# pqm_v2_page1.net
KiCad netlist of a schematic drawn in Altium Designer
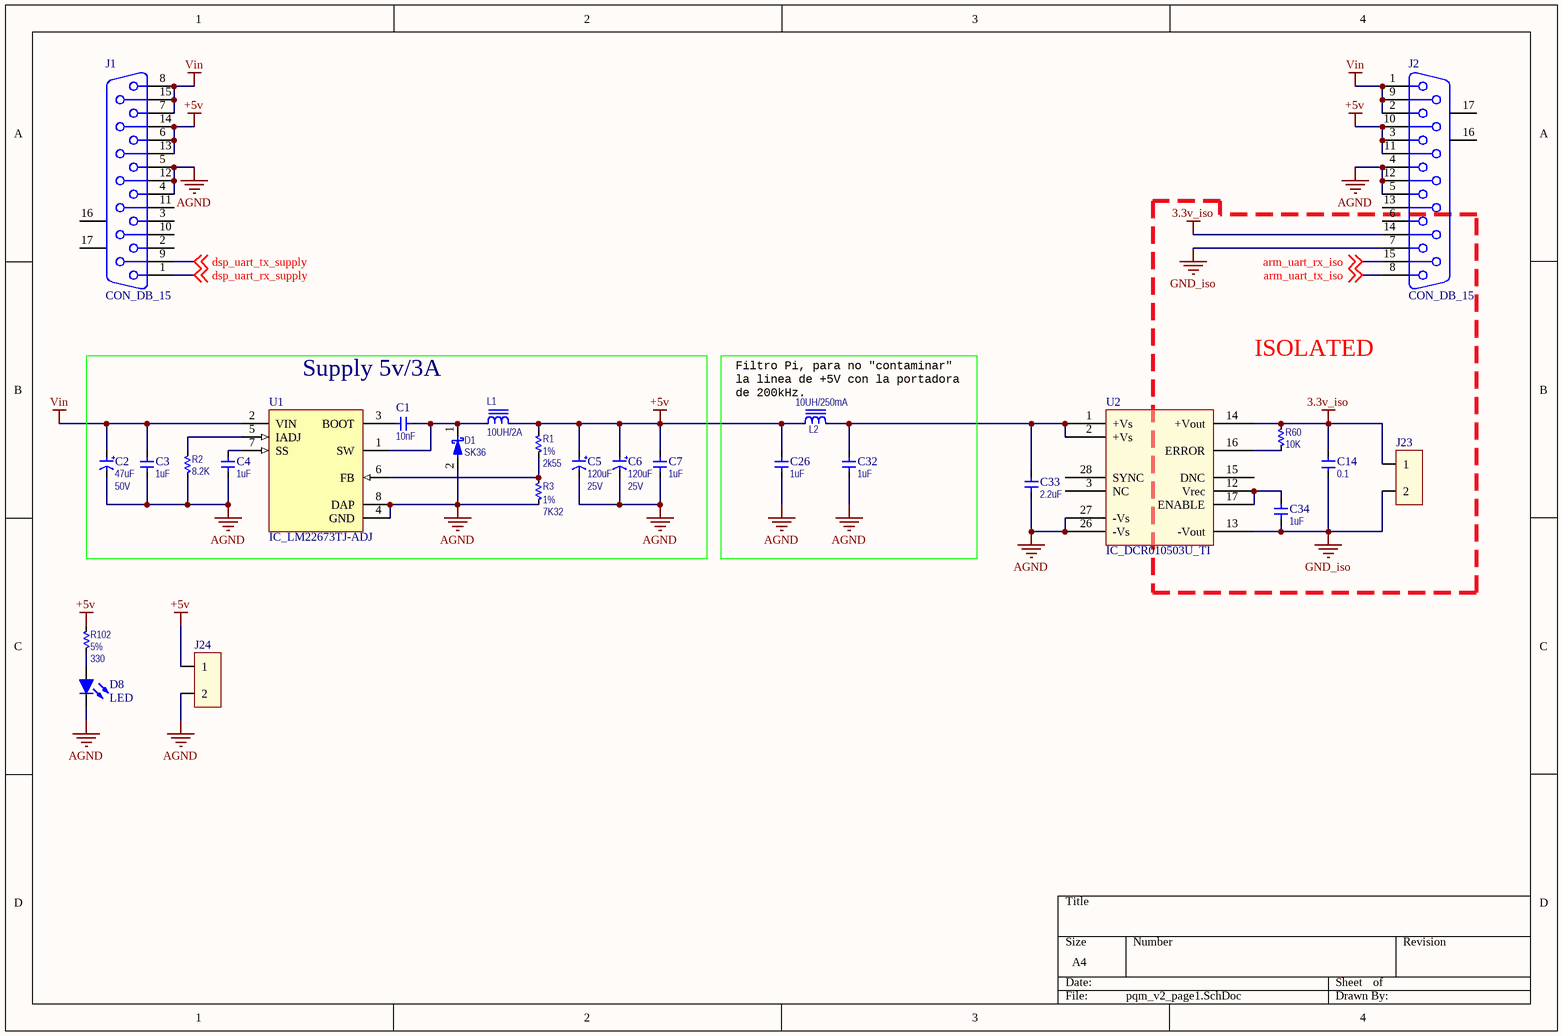
[diagram p0: pqm_v2_page1.SchDoc]

(export (version "E")
  (design (tool "Eeschema 10.0.6"))
  (components
    (comp (ref "C1")
      (value "10nF")
      (footprint "CAPC3216X135N_B")
      (fields
        (field (name "MANUFACTURER") "TDK")
        (field (name "TOLERANCE") "10%")
        (field (name "DIGIKEY PART NUMBER") "445-2291-1-ND")
      )
      (libsource (lib "pqm_v2_lib_cap") (part "CAP_C3216X7R2J103K115AA_TDK"))
    )
    (comp (ref "C2")
      (value "47uF")
      (footprint "CAPAE630770X770N")
      (description "47µF 50V Aluminum Capacitors Radial, Can - SMD 2000 Hrs @ 85°C")
      (fields
        (field (name "MANUFACTURER") "Panasonic")
        (field (name "TOLERANCE") "20%")
        (field (name "VOLTAGE RATING") "50V")
      )
      (libsource (lib "pqm_v2_lib_cap") (part "CAP_EEE-1HA470XP_PANASONIC"))
    )
    (comp (ref "C3")
      (value "1uF")
      (footprint "CAPC3216X135N_B")
      (fields
        (field (name "MANUFACTURER") "TDK")
        (field (name "TOLERANCE") "20%")
        (field (name "DIGIKEY PART NUMBER") "445-4024-1-ND")
      )
      (libsource (lib "pqm_v2_lib_cap") (part "CAP_C3216X7R1E105M085AA_TDK"))
    )
    (comp (ref "C4")
      (value "1uF")
      (footprint "CAPC3216X135N_B")
      (fields
        (field (name "MANUFACTURER") "TDK")
        (field (name "TOLERANCE") "20%")
        (field (name "DIGIKEY PART NUMBER") "445-4024-1-ND")
      )
      (libsource (lib "pqm_v2_lib_cap") (part "CAP_C3216X7R1E105M085AA_TDK"))
    )
    (comp (ref "C5")
      (value "120uF")
      (footprint "CAPPRD250W50D630H1250")
      (description "CAP ALUM 120UF 20% 25V RADIAL")
      (fields
        (field (name "DIGIKEY PART NUMBER") "565-1791-ND")
        (field (name "TOLERANCE") "20%")
        (field (name "VOLTAGE RATING") "25V")
      )
      (libsource (lib "pqm_v2_lib_cap") (part "CAP_ELXY250ELL121MF15D_UC"))
    )
    (comp (ref "C6")
      (value "120uF")
      (footprint "CAPPRD250W50D630H1250")
      (description "CAP ALUM 120UF 20% 25V RADIAL")
      (fields
        (field (name "DIGIKEY PART NUMBER") "565-1791-ND")
        (field (name "TOLERANCE") "20%")
        (field (name "VOLTAGE RATING") "25V")
      )
      (libsource (lib "pqm_v2_lib_cap") (part "CAP_ELXY250ELL121MF15D_UC"))
    )
    (comp (ref "C7")
      (value "1uF")
      (footprint "CAPC3216X135N_B")
      (fields
        (field (name "MANUFACTURER") "TDK")
        (field (name "TOLERANCE") "20%")
        (field (name "DIGIKEY PART NUMBER") "445-4024-1-ND")
      )
      (libsource (lib "pqm_v2_lib_cap") (part "CAP_C3216X7R1E105M085AA_TDK"))
    )
    (comp (ref "C14")
      (value "0.1")
      (footprint "CAPC2013X110N")
      (description "CAP CER 0.1UF 25V 10% X7R 0805")
      (fields (field (name "MANUFACTURER") "Yageo") (field (name "TOLERANCE") "10%"))
      (libsource (lib "pqm_v2_lib_cap") (part "CAP_CC0805KRX7R8BB104_YAGEO"))
    )
    (comp (ref "C26")
      (value "1uF")
      (footprint "CAPC3216X135N_B")
      (fields
        (field (name "MANUFACTURER") "TDK")
        (field (name "TOLERANCE") "20%")
        (field (name "DIGIKEY PART NUMBER") "445-4024-1-ND")
      )
      (libsource (lib "pqm_v2_lib_cap") (part "CAP_C3216X7R1E105M085AA_TDK"))
    )
    (comp (ref "C32")
      (value "1uF")
      (footprint "CAPC3216X135N_B")
      (fields
        (field (name "MANUFACTURER") "TDK")
        (field (name "TOLERANCE") "20%")
        (field (name "DIGIKEY PART NUMBER") "445-4024-1-ND")
      )
      (libsource (lib "pqm_v2_lib_cap") (part "CAP_C3216X7R1E105M085AA_TDK"))
    )
    (comp (ref "C33")
      (value "2.2uF")
      (footprint "CAPC3216X135N_B")
      (description "CAP CER 2.2UF 16V X7R 1206")
      (fields (field (name "MANUFACTURER") "YAGEO") (field (name "TOLERANCE") "10%"))
      (libsource (lib "pqm_v2_lib_cap") (part "CAP_CC1206KKX7R7BB225_YAGEO"))
    )
    (comp (ref "C34")
      (value "1uF")
      (footprint "CAPC2013X110N")
      (description "CAP CER 1UF 16V X7R 0805")
      (fields (field (name "MANUFACTURER") "YAGEO") (field (name "TOLERANCE") "10%"))
      (libsource (lib "pqm_v2_lib_cap") (part "CAP_CC0805KKX7R7BB105_YAGEO"))
    )
    (comp (ref "D1")
      (value "SK36")
      (footprint "DIOM7959X262N")
      (description "DIODE SCHOTTKY 60V 3A SMC")
      (fields
        (field (name "MANUFACTURER") "Micro Commercial Co")
        (field (name "DIGIKEY PART NUMBER") "SK36-TPMSCT-ND")
      )
      (libsource (lib "pqm_v2_lib_diodos") (part "DIO_SK36_MICROCOM"))
    )
    (comp (ref "D8")
      (value "LED")
      (footprint "Led")
      (fields (field (name "PUBLISHER") "Altium Limited"))
      (libsource (lib "pqm_v2_lib_diodos") (part "LED0"))
    )
    (comp (ref "J1")
      (value "CON_DB_15")
      (footprint "788757-1")
      (description "Receptacle Assembly, 15 Position, Right Angle, 8.08mm Series, Amplimite, with Screwlocks")
      (fields (field (name "PUBLISHER") "Altium Limited"))
      (libsource (lib "pqm_v2_lib_connectors") (part "788781-1"))
    )
    (comp (ref "J2")
      (value "CON_DB_15")
      (footprint "788757-1")
      (description "Receptacle Assembly, 15 Position, Right Angle, 8.08mm Series, Amplimite, with Screwlocks")
      (fields (field (name "PUBLISHER") "Altium Limited"))
      (libsource (lib "pqm_v2_lib_connectors") (part "788781-1"))
    )
    (comp (ref "J23")
      (value "CON_RADX2")
      (footprint "RAD2")
      (libsource (lib "pqm_v2_lib_connectors") (part "CON_RADX2"))
    )
    (comp (ref "J24")
      (value "CON_RADX2")
      (footprint "RAD2")
      (libsource (lib "pqm_v2_lib_connectors") (part "CON_RADX2"))
    )
    (comp (ref "L1")
      (value "10UH/2A")
      (footprint "MAG_INDUCTOR2A")
      (description "FIXED IND 10UH 2A 65 MOHM SMD")
      (fields
        (field (name "MANUFACTURER") "Bourns Inc")
        (field (name "DIGIKEY PART NUMBER") "SRR1005-100MCT-ND")
      )
      (libsource (lib "pqm_v2_lib_mag") (part "MAG_SRR1005-100M_BOURNS"))
    )
    (comp (ref "L2")
      (value "10UH/250mA")
      (footprint "INDC4532X170N")
      (description "FIXED IND 10UH 2A 65 MOHM SMD")
      (fields
        (field (name "MANUFACTURER") "Bourns Inc")
        (field (name "DIGIKEY PART NUMBER") "CM453232-100KLCT-ND")
      )
      (libsource (lib "pqm_v2_lib_mag") (part "MAG_CM453232-100KLCT_BOURNS"))
    )
    (comp (ref "R1")
      (value "2k55")
      (footprint "RESC3216N")
      (description "RES SMD 2.55K OHM 1% 1/4W 1206")
      (fields
        (field (name "MANUFACTURER") "Panasonic")
        (field (name "DIGIKEY PART NUMBER") "P2.55KFCT-ND")
        (field (name "TOLERANCE") "1%")
      )
      (libsource (lib "pqm_v2_lib_res") (part "RES_ERJ-8ENF2551V_Panasonic"))
    )
    (comp (ref "R2")
      (value "8.2K")
      (footprint "RESC3216N")
      (description "RES SMD 8.2K OHM 5% 1/4W 1206")
      (fields (field (name "TOLERANCE") "5%") (field (name "MANUFACTURER") "Panasonic"))
      (libsource (lib "pqm_v2_lib_res") (part "RES_ERJ-8GEYJ822V_Panasonic"))
    )
    (comp (ref "R3")
      (value "7K32")
      (footprint "RESC3216N")
      (description "RES SMD 7.32K OHM 1% 1/4W 1206")
      (fields
        (field (name "MANUFACTURER") "Panasonic")
        (field (name "DIGIKEY PART NUMBER") "P7.32KFCT-ND")
        (field (name "TOLERANCE") "1%")
      )
      (libsource (lib "pqm_v2_lib_res") (part "RES_ERJ-8ENF7321V_Panasonic"))
    )
    (comp (ref "R60")
      (value "10K")
      (footprint "RESC3216N")
      (description "RES SMD 10K OHM 1% 1/4W 1206")
      (fields (field (name "TOLERANCE") "1%") (field (name "MANUFACTURER") "Yageo"))
      (libsource (lib "pqm_v2_lib_res") (part "RES_RC1206FR-0710KL_Yageo"))
    )
    (comp (ref "R102")
      (value "330")
      (footprint "RESC2013X065BN")
      (description "RES SMD 330 OHM 5% 1/8W 0805")
      (fields
        (field (name "MANUFACTURER") "Yageo")
        (field (name "DIGIKEY PART NUMBER") "311-330ARCT-ND")
        (field (name "TOLERANCE") "5%")
      )
      (libsource (lib "pqm_v2_lib_res") (part "RES_RC0805JR-07330RL_YAGEO"))
    )
    (comp (ref "U1")
      (value "IC_LM22673TJ-ADJ")
      (footprint "TJ7A_N")
      (fields
        (field (name "DIGIKEY PART NUMBER") "LM22673TJ-ADJ/NOPBCT-ND")
        (field (name "MANUFACTURER PART NUMBER") "LM22673TJ-ADJ/NOPB")
        (field (name "MOUSER PART NUMBER") "926-LM22673TJADJNOPB")
      )
      (libsource (lib "pqm_v2_lib_ic") (part "IC_LM22673TJ-ADJ"))
    )
    (comp (ref "U2")
      (value "IC_DCR010503U_TI")
      (footprint "SOP28")
      (description "IC REG ISOLATED 3.3V 0.3A 12SOP")
      (fields
        (field (name "DIGIKEY PART NUMBER") "296-9450-5-ND")
        (field (name "MOUSER PART NUMBER") "595-DCR010503U")
      )
      (libsource (lib "pqm_v2_lib_ic") (part "IC_DCR010503U_TI"))
    )
  )
  (nets
    (net (code "1") (name "+5v") (class "Default")
      (node (ref "C26") (pin "1") (pinfunction "T1_1") (pintype "passive"))
      (node (ref "C5") (pin "1") (pinfunction "1_1") (pintype "passive"))
      (node (ref "C6") (pin "1") (pinfunction "1_1") (pintype "passive"))
      (node (ref "C7") (pin "1") (pinfunction "T1_1") (pintype "passive"))
      (node (ref "J1") (pin "13") (pinfunction "13_13") (pintype "passive"))
      (node (ref "J1") (pin "14") (pinfunction "14_14") (pintype "passive"))
      (node (ref "J1") (pin "6") (pinfunction "6_6") (pintype "passive"))
      (node (ref "J2") (pin "10") (pinfunction "10_10") (pintype "passive"))
      (node (ref "J2") (pin "11") (pinfunction "11_11") (pintype "passive"))
      (node (ref "J2") (pin "3") (pinfunction "3_3") (pintype "passive"))
      (node (ref "J24") (pin "1") (pinfunction "1_1") (pintype "passive"))
      (node (ref "L1") (pin "2") (pinfunction "2_2") (pintype "passive"))
      (node (ref "L2") (pin "1") (pinfunction "1_1") (pintype "passive"))
      (node (ref "R1") (pin "1") (pinfunction "T1_1") (pintype "passive"))
      (node (ref "R102") (pin "2") (pinfunction "T2_2") (pintype "passive"))
    )
    (net (code "2") (name "3.3v_iso") (class "Default")
      (node (ref "C14") (pin "1") (pinfunction "T1_1") (pintype "passive"))
      (node (ref "J2") (pin "14") (pinfunction "14_14") (pintype "passive"))
      (node (ref "J23") (pin "1") (pinfunction "1_1") (pintype "passive"))
      (node (ref "R60") (pin "2") (pinfunction "T2_2") (pintype "passive"))
      (node (ref "U2") (pin "14") (pinfunction "+Vout_14") (pintype "passive"))
    )
    (net (code "3") (name "AGND") (class "Default")
      (node (ref "C2") (pin "2") (pinfunction "2_2") (pintype "passive"))
      (node (ref "C26") (pin "2") (pinfunction "T2_2") (pintype "passive"))
      (node (ref "C3") (pin "2") (pinfunction "T2_2") (pintype "passive"))
      (node (ref "C32") (pin "2") (pinfunction "T2_2") (pintype "passive"))
      (node (ref "C33") (pin "2") (pinfunction "T2_2") (pintype "passive"))
      (node (ref "C4") (pin "2") (pinfunction "T2_2") (pintype "passive"))
      (node (ref "C5") (pin "2") (pinfunction "2_2") (pintype "passive"))
      (node (ref "C6") (pin "2") (pinfunction "2_2") (pintype "passive"))
      (node (ref "C7") (pin "2") (pinfunction "T2_2") (pintype "passive"))
      (node (ref "D1") (pin "2") (pinfunction "A_2") (pintype "passive"))
      (node (ref "D8") (pin "2") (pinfunction "K_2") (pintype "passive"))
      (node (ref "J1") (pin "12") (pinfunction "12_12") (pintype "passive"))
      (node (ref "J1") (pin "4") (pinfunction "4_4") (pintype "passive"))
      (node (ref "J1") (pin "5") (pinfunction "5_5") (pintype "passive"))
      (node (ref "J2") (pin "12") (pinfunction "12_12") (pintype "passive"))
      (node (ref "J2") (pin "4") (pinfunction "4_4") (pintype "passive"))
      (node (ref "J2") (pin "5") (pinfunction "5_5") (pintype "passive"))
      (node (ref "J24") (pin "2") (pinfunction "2_2") (pintype "passive"))
      (node (ref "R2") (pin "1") (pinfunction "T1_1") (pintype "passive"))
      (node (ref "R3") (pin "2") (pinfunction "T2_2") (pintype "passive"))
      (node (ref "U1") (pin "4") (pinfunction "GND_4") (pintype "power_in"))
      (node (ref "U1") (pin "8") (pinfunction "DAP_8") (pintype "power_in"))
      (node (ref "U2") (pin "26") (pinfunction "-Vs_26") (pintype "passive"))
      (node (ref "U2") (pin "27") (pinfunction "-Vs_27") (pintype "passive"))
    )
    (net (code "4") (name "GND_iso") (class "Default")
      (node (ref "C14") (pin "2") (pinfunction "T2_2") (pintype "passive"))
      (node (ref "C34") (pin "2") (pinfunction "T2_2") (pintype "passive"))
      (node (ref "J2") (pin "7") (pinfunction "7_7") (pintype "passive"))
      (node (ref "J23") (pin "2") (pinfunction "2_2") (pintype "passive"))
      (node (ref "U2") (pin "13") (pinfunction "-Vout_13") (pintype "passive"))
    )
    (net (code "5") (name "Net-(C1-T1)") (class "Default")
      (node (ref "C1") (pin "1") (pinfunction "T1_1") (pintype "passive"))
      (node (ref "U1") (pin "3") (pinfunction "BOOT_3") (pintype "passive"))
    )
    (net (code "6") (name "Net-(C1-T2)") (class "Default")
      (node (ref "C1") (pin "2") (pinfunction "T2_2") (pintype "passive"))
      (node (ref "D1") (pin "1") (pinfunction "K_1") (pintype "passive"))
      (node (ref "L1") (pin "1") (pinfunction "1_1") (pintype "passive"))
      (node (ref "U1") (pin "1") (pinfunction "SW_1") (pintype "power_in"))
    )
    (net (code "7") (name "Net-(C4-T1)") (class "Default")
      (node (ref "C4") (pin "1") (pinfunction "T1_1") (pintype "passive"))
      (node (ref "U1") (pin "7") (pinfunction "SS_7") (pintype "input"))
    )
    (net (code "8") (name "Net-(C32-T1)") (class "Default")
      (node (ref "C32") (pin "1") (pinfunction "T1_1") (pintype "passive"))
      (node (ref "C33") (pin "1") (pinfunction "T1_1") (pintype "passive"))
      (node (ref "L2") (pin "2") (pinfunction "2_2") (pintype "passive"))
      (node (ref "U2") (pin "1") (pinfunction "+Vs_1") (pintype "passive"))
      (node (ref "U2") (pin "2") (pinfunction "+Vs_2") (pintype "passive"))
    )
    (net (code "9") (name "Net-(C34-T1)") (class "Default")
      (node (ref "C34") (pin "1") (pinfunction "T1_1") (pintype "passive"))
      (node (ref "U2") (pin "12") (pinfunction "Vrec_12") (pintype "passive"))
      (node (ref "U2") (pin "17") (pinfunction "ENABLE_17") (pintype "passive"))
    )
    (net (code "10") (name "Net-(D8-A)") (class "Default")
      (node (ref "D8") (pin "1") (pinfunction "A_1") (pintype "passive"))
      (node (ref "R102") (pin "1") (pinfunction "T1_1") (pintype "passive"))
    )
    (net (code "11") (name "Net-(R1-T2)") (class "Default")
      (node (ref "R1") (pin "2") (pinfunction "T2_2") (pintype "passive"))
      (node (ref "R3") (pin "1") (pinfunction "T1_1") (pintype "passive"))
      (node (ref "U1") (pin "6") (pinfunction "FB_6") (pintype "input"))
    )
    (net (code "12") (name "Net-(R2-T2)") (class "Default")
      (node (ref "R2") (pin "2") (pinfunction "T2_2") (pintype "passive"))
      (node (ref "U1") (pin "5") (pinfunction "IADJ_5") (pintype "input"))
    )
    (net (code "13") (name "Net-(R60-T1)") (class "Default")
      (node (ref "R60") (pin "1") (pinfunction "T1_1") (pintype "passive"))
      (node (ref "U2") (pin "16") (pinfunction "ERROR_16") (pintype "passive"))
    )
    (net (code "14") (name "Vin") (class "Default")
      (node (ref "C2") (pin "1") (pinfunction "1_1") (pintype "passive"))
      (node (ref "C3") (pin "1") (pinfunction "T1_1") (pintype "passive"))
      (node (ref "J1") (pin "15") (pinfunction "15_15") (pintype "passive"))
      (node (ref "J1") (pin "7") (pinfunction "7_7") (pintype "passive"))
      (node (ref "J1") (pin "8") (pinfunction "8_8") (pintype "passive"))
      (node (ref "J2") (pin "1") (pinfunction "1_1") (pintype "passive"))
      (node (ref "J2") (pin "2") (pinfunction "2_2") (pintype "passive"))
      (node (ref "J2") (pin "9") (pinfunction "9_9") (pintype "passive"))
      (node (ref "U1") (pin "2") (pinfunction "VIN_2") (pintype "power_in"))
    )
    (net (code "15") (name "arm_uart_rx_iso") (class "Default")
      (node (ref "J2") (pin "15") (pinfunction "15_15") (pintype "passive"))
    )
    (net (code "16") (name "arm_uart_tx_iso") (class "Default")
      (node (ref "J2") (pin "8") (pinfunction "8_8") (pintype "passive"))
    )
    (net (code "17") (name "dsp_uart_rx_supply") (class "Default")
      (node (ref "J1") (pin "1") (pinfunction "1_1") (pintype "passive"))
    )
    (net (code "18") (name "dsp_uart_tx_supply") (class "Default")
      (node (ref "J1") (pin "9") (pinfunction "9_9") (pintype "passive"))
    )
    (net (code "19") (name "unconnected-(J1-MH1-Pad16)") (class "Default")
      (node (ref "J1") (pin "16") (pinfunction "MH1_16") (pintype "passive"))
    )
    (net (code "20") (name "unconnected-(J1-MH2-Pad17)") (class "Default")
      (node (ref "J1") (pin "17") (pinfunction "MH2_17") (pintype "passive"))
    )
    (net (code "21") (name "unconnected-(J1-Pad2)") (class "Default")
      (node (ref "J1") (pin "2") (pinfunction "2_2") (pintype "passive"))
    )
    (net (code "22") (name "unconnected-(J1-Pad3)") (class "Default")
      (node (ref "J1") (pin "3") (pinfunction "3_3") (pintype "passive"))
    )
    (net (code "23") (name "unconnected-(J1-Pad10)") (class "Default")
      (node (ref "J1") (pin "10") (pinfunction "10_10") (pintype "passive"))
    )
    (net (code "24") (name "unconnected-(J1-Pad11)") (class "Default")
      (node (ref "J1") (pin "11") (pinfunction "11_11") (pintype "passive"))
    )
    (net (code "25") (name "unconnected-(J2-MH1-Pad16)") (class "Default")
      (node (ref "J2") (pin "16") (pinfunction "MH1_16") (pintype "passive"))
    )
    (net (code "26") (name "unconnected-(J2-MH2-Pad17)") (class "Default")
      (node (ref "J2") (pin "17") (pinfunction "MH2_17") (pintype "passive"))
    )
    (net (code "27") (name "unconnected-(J2-Pad6)") (class "Default")
      (node (ref "J2") (pin "6") (pinfunction "6_6") (pintype "passive"))
    )
    (net (code "28") (name "unconnected-(J2-Pad13)") (class "Default")
      (node (ref "J2") (pin "13") (pinfunction "13_13") (pintype "passive"))
    )
    (net (code "29") (name "unconnected-(U2-DNC-Pad15)") (class "Default")
      (node (ref "U2") (pin "15") (pinfunction "DNC_15") (pintype "passive"))
    )
    (net (code "30") (name "unconnected-(U2-NC-Pad3)") (class "Default")
      (node (ref "U2") (pin "3") (pinfunction "NC_3") (pintype "passive"))
    )
    (net (code "31") (name "unconnected-(U2-SYNC-Pad28)") (class "Default")
      (node (ref "U2") (pin "28") (pinfunction "SYNC_28") (pintype "passive"))
    )
  )
)
